# PCB_RLC_LPF.net
KiCad netlist of a schematic drawn in Altium Designer
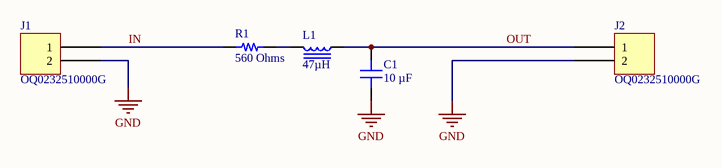
[diagram p0: PCB_RLC_LPF.SchDoc]

(export (version "E")
  (design (tool "Eeschema 10.0.6"))
  (components
    (comp (ref "C1")
      (value "10 µF")
      (footprint "CAP 0603_1608")
      (description "CAP CER 10UF 10V X5R 0603")
      (fields
        (field (name "PART NUMBER") "MD0603BW106M100NHT-EM")
        (field (name "MANUFACTURER") "Knowles Novacap")
      )
      (libsource (lib "Celestial Altium Library - altium_library") (part "Capacitor"))
    )
    (comp (ref "J1")
      (value "OQ0232510000G")
      (footprint "FCI 06-381-2PIN")
      (description "TERM BLOCK HDR 2POS 90DEG 3.81MM")
      (fields (field (name "MANUFACTURER") "Amphenol Anytek"))
      (libsource (lib "") (part "2 Pin_1"))
    )
    (comp (ref "J2")
      (value "OQ0232510000G")
      (footprint "FCI 06-381-2PIN")
      (description "TERM BLOCK HDR 2POS 90DEG 3.81MM")
      (fields (field (name "MANUFACTURER") "Amphenol Anytek"))
      (libsource (lib "Celestial Altium Library - altium_library") (part "2 Pin"))
    )
    (comp (ref "L1")
      (value "47µH")
      (footprint "IND 0603_1608 RF WW")
      (description "INDUCTORPOWER LINE 0603 47H 20%")
      (fields (field (name "PART NUMBER") "L0603B470MPWFT") (field (name "MANUFACTURER") "KEMET"))
      (libsource (lib "Celestial Altium Library - altium_library") (part "Inductor"))
    )
    (comp (ref "R1")
      (value "560 Ohms")
      (footprint "RES 0603_1608")
      (description "RES 560 OHM 1% 1/4W 0603")
      (fields
        (field (name "PART NUMBER") "CRGP0603F560R")
        (field (name "MANUFACTURER") "TE Connectivity Passive Product")
      )
      (libsource (lib "Celestial Altium Library - altium_library") (part "Resistor"))
    )
  )
  (nets
    (net (code "1") (name "/IN") (class "Default")
      (node (ref "J1") (pin "1") (pinfunction "1_1") (pintype "passive"))
      (node (ref "R1") (pin "1") (pinfunction "1_1") (pintype "passive"))
    )
    (net (code "2") (name "/OUT") (class "Default")
      (node (ref "C1") (pin "2") (pinfunction "2_2") (pintype "passive"))
      (node (ref "J2") (pin "1") (pinfunction "1_1") (pintype "passive"))
      (node (ref "L1") (pin "1") (pinfunction "1_1") (pintype "passive"))
    )
    (net (code "3") (name "GND") (class "Default")
      (node (ref "C1") (pin "1") (pinfunction "1_1") (pintype "passive"))
      (node (ref "J1") (pin "2") (pinfunction "2_2") (pintype "passive"))
      (node (ref "J2") (pin "2") (pinfunction "2_2") (pintype "passive"))
    )
    (net (code "4") (name "Net-(L1-Pad2)") (class "Default")
      (node (ref "L1") (pin "2") (pinfunction "2_2") (pintype "passive"))
      (node (ref "R1") (pin "2") (pinfunction "2_2") (pintype "passive"))
    )
  )
)
